# DENAS_Scheme.net
KiCad netlist of a schematic drawn in Altium Designer
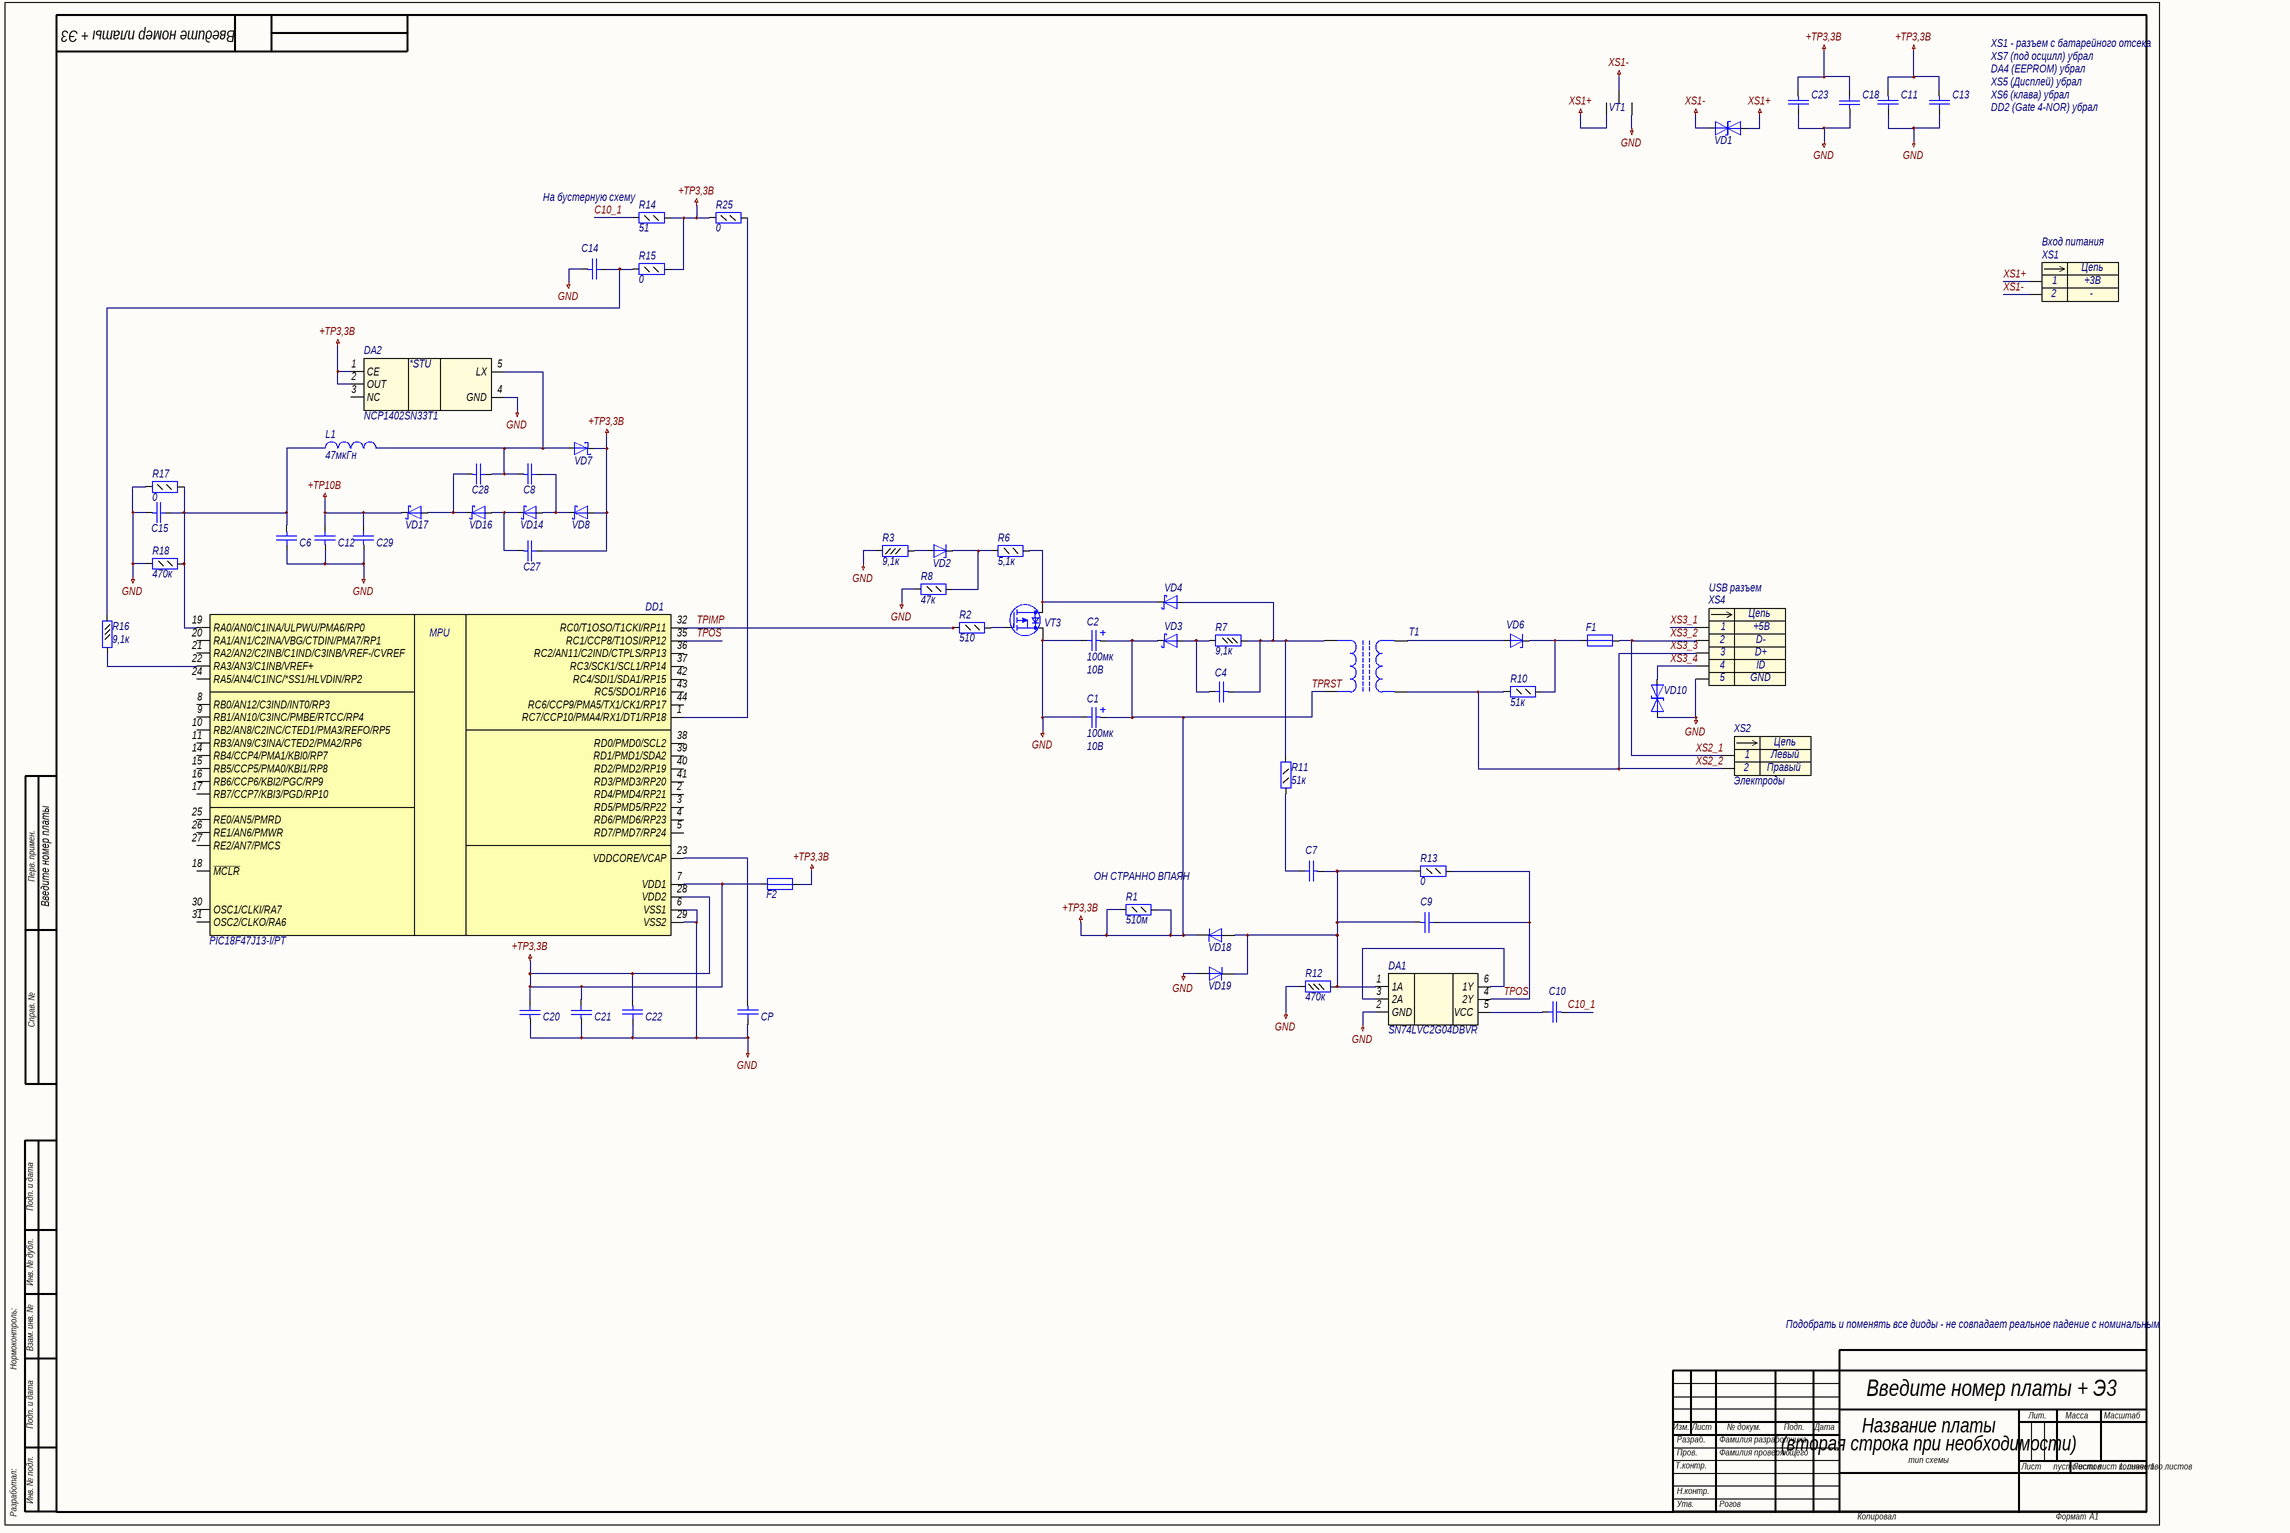
[diagram p0: DENAS_Scheme.SchDoc]

(export (version "E")
  (design (tool "Eeschema 10.0.6"))
  (components
    (comp (ref "C1")
      (value "100мк")
      (footprint "TANTAL CASE D")
      (description "Конденсатор полярный")
      (fields
        (field (name "VOLTAGE") "10В")
        (field (name "PART NUMBER") "T495D107K010ATA080")
        (field (name "Comment") "Capacitor_pol")
      )
      (libsource (lib "MOP44") (part "Capacitor_pol"))
    )
    (comp (ref "C2")
      (value "100мк")
      (footprint "TANTAL CASE D")
      (description "Конденсатор полярный")
      (fields
        (field (name "VOLTAGE") "10В")
        (field (name "PART NUMBER") "T495D107K010ATA080")
        (field (name "Comment") "Capacitor_pol")
      )
      (libsource (lib "MOP44") (part "Capacitor_pol"))
    )
    (comp (ref "C4")
      (value "Capacitor")
      (footprint "C0402")
      (description "Конденсатор")
      (fields (field (name "VOLTAGE") "50B") (field (name "PART NUMBER") "GRP1555C1HR47CZ01E"))
      (libsource (lib "MOP44") (part "Capacitor"))
    )
    (comp (ref "C6")
      (value "Capacitor")
      (footprint "C0402")
      (description "Конденсатор")
      (fields (field (name "VOLTAGE") "50B") (field (name "PART NUMBER") "GRP1555C1HR47CZ01E"))
      (libsource (lib "MOP44") (part "Capacitor"))
    )
    (comp (ref "C7")
      (value "Capacitor")
      (footprint "C0402")
      (description "Конденсатор")
      (fields (field (name "VOLTAGE") "50B") (field (name "PART NUMBER") "GRP1555C1HR47CZ01E"))
      (libsource (lib "MOP44") (part "Capacitor"))
    )
    (comp (ref "C8")
      (value "Capacitor")
      (footprint "C0402")
      (description "Конденсатор")
      (fields (field (name "VOLTAGE") "50B") (field (name "PART NUMBER") "GRP1555C1HR47CZ01E"))
      (libsource (lib "MOP44") (part "Capacitor"))
    )
    (comp (ref "C9")
      (value "Capacitor")
      (footprint "C0402")
      (description "Конденсатор")
      (fields (field (name "VOLTAGE") "50B") (field (name "PART NUMBER") "GRP1555C1HR47CZ01E"))
      (libsource (lib "MOP44") (part "Capacitor"))
    )
    (comp (ref "C10")
      (value "Capacitor")
      (footprint "C0402")
      (description "Конденсатор")
      (fields (field (name "VOLTAGE") "50B") (field (name "PART NUMBER") "GRP1555C1HR47CZ01E"))
      (libsource (lib "MOP44") (part "Capacitor"))
    )
    (comp (ref "C11")
      (value "Capacitor")
      (footprint "C0402")
      (description "Конденсатор")
      (fields (field (name "VOLTAGE") "50B") (field (name "PART NUMBER") "GRP1555C1HR47CZ01E"))
      (libsource (lib "MOP44") (part "Capacitor"))
    )
    (comp (ref "C12")
      (value "Capacitor")
      (footprint "C0402")
      (description "Конденсатор")
      (fields (field (name "VOLTAGE") "50B") (field (name "PART NUMBER") "GRP1555C1HR47CZ01E"))
      (libsource (lib "MOP44") (part "Capacitor"))
    )
    (comp (ref "C13")
      (value "Capacitor")
      (footprint "C0402")
      (description "Конденсатор")
      (fields (field (name "VOLTAGE") "50B") (field (name "PART NUMBER") "GRP1555C1HR47CZ01E"))
      (libsource (lib "MOP44") (part "Capacitor"))
    )
    (comp (ref "C14")
      (value "Capacitor")
      (footprint "C0402")
      (description "Конденсатор")
      (fields (field (name "VOLTAGE") "50B") (field (name "PART NUMBER") "GRP1555C1HR47CZ01E"))
      (libsource (lib "MOP44") (part "Capacitor"))
    )
    (comp (ref "C15")
      (value "Capacitor")
      (footprint "C0402")
      (description "Конденсатор")
      (fields (field (name "VOLTAGE") "50B") (field (name "PART NUMBER") "GRP1555C1HR47CZ01E"))
      (libsource (lib "MOP44") (part "Capacitor"))
    )
    (comp (ref "C18")
      (value "Capacitor")
      (footprint "C0402")
      (description "Конденсатор")
      (fields (field (name "VOLTAGE") "50B") (field (name "PART NUMBER") "GRP1555C1HR47CZ01E"))
      (libsource (lib "MOP44") (part "Capacitor"))
    )
    (comp (ref "C20")
      (value "Capacitor")
      (footprint "C0402")
      (description "Конденсатор")
      (fields (field (name "VOLTAGE") "50B") (field (name "PART NUMBER") "GRP1555C1HR47CZ01E"))
      (libsource (lib "MOP44") (part "Capacitor"))
    )
    (comp (ref "C21")
      (value "Capacitor")
      (footprint "C0402")
      (description "Конденсатор")
      (fields (field (name "VOLTAGE") "50B") (field (name "PART NUMBER") "GRP1555C1HR47CZ01E"))
      (libsource (lib "MOP44") (part "Capacitor"))
    )
    (comp (ref "C22")
      (value "Capacitor")
      (footprint "C0402")
      (description "Конденсатор")
      (fields (field (name "VOLTAGE") "50B") (field (name "PART NUMBER") "GRP1555C1HR47CZ01E"))
      (libsource (lib "MOP44") (part "Capacitor"))
    )
    (comp (ref "C23")
      (value "Capacitor")
      (footprint "C0402")
      (description "Конденсатор")
      (fields (field (name "VOLTAGE") "50B") (field (name "PART NUMBER") "GRP1555C1HR47CZ01E"))
      (libsource (lib "MOP44") (part "Capacitor"))
    )
    (comp (ref "C27")
      (value "Capacitor")
      (footprint "C0402")
      (description "Конденсатор")
      (fields (field (name "VOLTAGE") "50B") (field (name "PART NUMBER") "GRP1555C1HR47CZ01E"))
      (libsource (lib "MOP44") (part "Capacitor"))
    )
    (comp (ref "C28")
      (value "Capacitor")
      (footprint "C0402")
      (description "Конденсатор")
      (fields (field (name "VOLTAGE") "50B") (field (name "PART NUMBER") "GRP1555C1HR47CZ01E"))
      (libsource (lib "MOP44") (part "Capacitor"))
    )
    (comp (ref "C29")
      (value "Capacitor")
      (footprint "C0402")
      (description "Конденсатор")
      (fields (field (name "VOLTAGE") "50B") (field (name "PART NUMBER") "GRP1555C1HR47CZ01E"))
      (libsource (lib "MOP44") (part "Capacitor"))
    )
    (comp (ref "CP")
      (value "Capacitor")
      (footprint "C0402")
      (description "Конденсатор")
      (fields (field (name "VOLTAGE") "50B") (field (name "PART NUMBER") "GRP1555C1HR47CZ01E"))
      (libsource (lib "MOP44") (part "Capacitor"))
    )
    (comp (ref "DA1")
      (value "SN74LVC2G04DBVR")
      (footprint "SOT23-6")
      (description "Инвертирующий Триггер Шмитта")
      (fields (field (name "PART NUMBER") "SN74LVC2G04DBVR"))
      (libsource (lib "MOP44") (part "SN74LVC2G04DBVR"))
    )
    (comp (ref "DA2")
      (value "NCP1402")
      (footprint "SOT23-5")
      (description "Step-up DC-DC Converter for 2-V to 3.3-V")
      (fields (field (name "PART NUMBER") "NCP1402SN33T1") (field (name "MANUFACTURER") "ON Semiconductor"))
      (libsource (lib "MOP44") (part "NCP1402"))
    )
    (comp (ref "DD1")
      (value "PIC18F47J13-I/PT")
      (footprint "TQFP-44")
      (description "Микроконтроллер 8-Бит, 44-pin")
      (libsource (lib "MOP44") (part "PIC18F47J13-I/PT"))
    )
    (comp (ref "F1")
      (value "Fuse")
      (footprint "FUSE812")
      (description "Предохранитель")
      (fields (field (name "PART NUMBER") "MF-MSMF050"))
      (libsource (lib "") (part "Fuse_1"))
    )
    (comp (ref "F2")
      (value "Fuse")
      (footprint "FUSE812")
      (description "Предохранитель")
      (fields (field (name "PART NUMBER") "MF-MSMF075"))
      (libsource (lib "MOP44") (part "Fuse"))
    )
    (comp (ref "L1")
      (value "47мкГн")
      (footprint "SDR0604")
      (description "EMI Suppression Filter")
      (fields (field (name "PART NUMBER") "SDR0604- 470KL") (field (name "Comment") "Inductor"))
      (libsource (lib "MOP44") (part "Inductor"))
    )
    (comp (ref "R1")
      (value "510м")
      (footprint "R0805")
      (description "Резистор")
      (fields (field (name "PART NUMBER") "RC0805FR-07510RL") (field (name "POWER") "0,125Вт"))
      (libsource (lib "MOP44") (part "Resistor_0,125Вт"))
    )
    (comp (ref "R2")
      (value "510")
      (footprint "R0805")
      (description "Резистор")
      (fields (field (name "PART NUMBER") "RC0805FR-07510RL") (field (name "POWER") "0,125Вт"))
      (libsource (lib "MOP44") (part "Resistor_0,125Вт"))
    )
    (comp (ref "R3")
      (value "9,1к")
      (footprint "R0603")
      (description "Резистор")
      (fields (field (name "PART NUMBER") "RC0603FR-079K1") (field (name "POWER") "0,062Вт"))
      (libsource (lib "") (part "Resistor_0,062Вт_3"))
    )
    (comp (ref "R6")
      (value "5,1к")
      (footprint "R0805")
      (description "Резистор")
      (fields (field (name "PART NUMBER") "RC0805FR-075K1") (field (name "POWER") "0,125Вт"))
      (libsource (lib "MOP44") (part "Resistor_0,125Вт"))
    )
    (comp (ref "R7")
      (value "9,1к")
      (footprint "R0603")
      (description "Резистор")
      (fields (field (name "PART NUMBER") "RC0603FR-079K1") (field (name "POWER") "0,062Вт"))
      (libsource (lib "MOP44") (part "Resistor_0,062Вт"))
    )
    (comp (ref "R8")
      (value "47к")
      (footprint "R0805")
      (description "Резистор")
      (fields (field (name "PART NUMBER") "RC0805FR-0747KL") (field (name "POWER") "0,125Вт"))
      (libsource (lib "MOP44") (part "Resistor_0,125Вт"))
    )
    (comp (ref "R10")
      (value "51к")
      (footprint "R0805")
      (description "Резистор")
      (fields (field (name "PART NUMBER") "RC0805FR-0751KL") (field (name "POWER") "0,125Вт"))
      (libsource (lib "MOP44") (part "Resistor_0,125Вт"))
    )
    (comp (ref "R11")
      (value "51к")
      (footprint "R0805")
      (description "Резистор")
      (fields (field (name "PART NUMBER") "RC0805FR-0751KL") (field (name "POWER") "0,125Вт"))
      (libsource (lib "") (part "Resistor_0,125Вт_2"))
    )
    (comp (ref "R12")
      (value "470к")
      (footprint "R0603")
      (description "Резистор")
      (fields (field (name "PART NUMBER") "RC0603FR-07470KL") (field (name "POWER") "0,062Вт"))
      (libsource (lib "") (part "Resistor_0,062Вт_2"))
    )
    (comp (ref "R13")
      (value "0")
      (footprint "R0805")
      (description "Резистор")
      (fields (field (name "PART NUMBER") "RC0805FR-070RL") (field (name "POWER") "0,125Вт"))
      (libsource (lib "MOP44") (part "Resistor_0,125Вт"))
    )
    (comp (ref "R14")
      (value "51")
      (footprint "R0805")
      (description "Резистор")
      (fields (field (name "PART NUMBER") "RC0805FR-0751RL") (field (name "POWER") "0,125Вт"))
      (libsource (lib "") (part "Resistor_0,125Вт_1"))
    )
    (comp (ref "R15")
      (value "0")
      (footprint "R0805")
      (description "Резистор")
      (fields (field (name "PART NUMBER") "RC0805FR-070RL") (field (name "POWER") "0,125Вт"))
      (libsource (lib "") (part "Resistor_0,125Вт_1"))
    )
    (comp (ref "R16")
      (value "9,1к")
      (footprint "R0603")
      (description "Резистор")
      (fields (field (name "PART NUMBER") "RC0603FR-079K1") (field (name "POWER") "0,062Вт"))
      (libsource (lib "") (part "Resistor_0,062Вт_1"))
    )
    (comp (ref "R17")
      (value "0")
      (footprint "R0805")
      (description "Резистор")
      (fields (field (name "PART NUMBER") "RC0805FR-070RL") (field (name "POWER") "0,125Вт"))
      (libsource (lib "") (part "Resistor_0,125Вт_1"))
    )
    (comp (ref "R18")
      (value "470к")
      (footprint "R0805")
      (description "Резистор")
      (fields (field (name "PART NUMBER") "RC0805FR-07470KL") (field (name "POWER") "0,125Вт"))
      (libsource (lib "MOP44") (part "Resistor_0,125Вт"))
    )
    (comp (ref "R25")
      (value "0")
      (footprint "R0805")
      (description "Резистор")
      (fields (field (name "PART NUMBER") "RC0805FR-070RL") (field (name "POWER") "0,125Вт"))
      (libsource (lib "") (part "Resistor_0,125Вт_1"))
    )
    (comp (ref "T1")
      (value "Transformer")
      (footprint "Transformer36mm")
      (description "EMI Suppression Filter")
      (libsource (lib "MOP44") (part "Transformer"))
    )
    (comp (ref "VD1")
      (value "DiodeZenerDual")
      (footprint "SMB")
      (description "Cтабилитрон (диод выпрямительный лавинный) двусторонний")
      (fields (field (name "PART NUMBER") "SMBJ8.5CA"))
      (libsource (lib "MOP44") (part "DiodeZenerDual"))
    )
    (comp (ref "VD2")
      (value "DiodeZener")
      (footprint "SOT23-3")
      (description "Cтабилитрон (лавинный выпрямительный диод) односторонний")
      (fields (field (name "PART NUMBER") "BZX84-C30"))
      (libsource (lib "MOP44") (part "DiodeZener"))
    )
    (comp (ref "VD3")
      (value "DiodeSchottky")
      (footprint "SOD-123")
      (description "Диод Шоттки")
      (fields (field (name "PART NUMBER") "MBR0540"))
      (libsource (lib "MOP44") (part "DiodeSchottky"))
    )
    (comp (ref "VD4")
      (value "DiodeSchottky")
      (footprint "SOD-123")
      (description "Диод Шоттки")
      (fields (field (name "PART NUMBER") "MBR0540"))
      (libsource (lib "MOP44") (part "DiodeSchottky"))
    )
    (comp (ref "VD6")
      (value "DiodeZener")
      (footprint "SOT23-3")
      (description "Cтабилитрон (лавинный выпрямительный диод) односторонний")
      (fields (field (name "PART NUMBER") "BZX84-C5V1"))
      (libsource (lib "MOP44") (part "DiodeZener"))
    )
    (comp (ref "VD7")
      (value "DiodeSchottky")
      (footprint "SOD-123")
      (description "Диод Шоттки")
      (fields (field (name "PART NUMBER") "MBR0520LT1"))
      (libsource (lib "MOP44") (part "DiodeSchottky"))
    )
    (comp (ref "VD8")
      (value "DiodeSchottky")
      (footprint "SOD-123")
      (description "Диод Шоттки")
      (fields (field (name "PART NUMBER") "MBR0520LT1"))
      (libsource (lib "MOP44") (part "DiodeSchottky"))
    )
    (comp (ref "VD10")
      (value "DiodeZenerDual")
      (footprint "SMB")
      (description "Cтабилитрон (диод выпрямительный лавинный) двусторонний")
      (fields (field (name "PART NUMBER") "SMBJ8.5CA"))
      (libsource (lib "MOP44") (part "DiodeZenerDual"))
    )
    (comp (ref "VD14")
      (value "DiodeSchottky")
      (footprint "SOD-123")
      (description "Диод Шоттки")
      (fields (field (name "PART NUMBER") "MBR0520LT1"))
      (libsource (lib "MOP44") (part "DiodeSchottky"))
    )
    (comp (ref "VD16")
      (value "DiodeSchottky")
      (footprint "SOD-123")
      (description "Диод Шоттки")
      (fields (field (name "PART NUMBER") "MBR0520LT1"))
      (libsource (lib "MOP44") (part "DiodeSchottky"))
    )
    (comp (ref "VD17")
      (value "DiodeSchottky")
      (footprint "SOD-123")
      (description "Диод Шоттки")
      (fields (field (name "PART NUMBER") "MBR0520LT1"))
      (libsource (lib "MOP44") (part "DiodeSchottky"))
    )
    (comp (ref "VD18")
      (value "Diode")
      (footprint "SOD-123")
      (description "Диод")
      (fields (field (name "PART NUMBER") "MMSD4148"))
      (libsource (lib "MOP44") (part "Diode"))
    )
    (comp (ref "VD19")
      (value "Diode")
      (footprint "SOD-123")
      (description "Диод")
      (fields (field (name "PART NUMBER") "MMSD4148"))
      (libsource (lib "MOP44") (part "Diode"))
    )
    (comp (ref "VT3")
      (value "P-MOSFET")
      (footprint "SOT23-3")
      (description "N-MOSFET")
      (fields
        (field (name "PART NUMBER") "IRLML2244TRPbF")
        (field (name "MANUFACTURER") "International Rectifier")
      )
      (libsource (lib "MOP44") (part "P-MOSFET"))
    )
    (comp (ref "XS1")
      (value "Вход питания")
      (footprint "CWF-2")
      (description "Разъем - 2 конт. вилка")
      (fields (field (name "PART NUMBER") "DS1069-2MVW6X"))
      (libsource (lib "MOP44") (part "Header_2_plg"))
    )
    (comp (ref "XS2")
      (value "Электроды")
      (footprint "CWF-2")
      (description "Разъем - 2 конт. вилка")
      (fields (field (name "PART NUMBER") "DS1069-2MVW6X"))
      (libsource (lib "MOP44") (part "Header_2_plg"))
    )
    (comp (ref "XS4")
      (value "USB разъем")
      (footprint "USB MINI AB RECEPTACLE")
      (description "USB Mini Type AB Receptacle")
      (fields (field (name "PART NUMBER") "UJ2-MABH-1-SMT-TR"))
      (libsource (lib "MOP44") (part "USB MINI RECEPTACLE"))
    )
  )
  (nets
    (net (code "1") (name "+TP3,3В") (class "Default")
      (node (ref "C1") (pin "1") (pinfunction "1_1") (pintype "passive"))
      (node (ref "C11") (pin "1") (pinfunction "1_1") (pintype "passive"))
      (node (ref "C13") (pin "1") (pinfunction "1_1") (pintype "passive"))
      (node (ref "C18") (pin "2") (pinfunction "2_2") (pintype "passive"))
      (node (ref "C2") (pin "1") (pinfunction "1_1") (pintype "passive"))
      (node (ref "C20") (pin "2") (pinfunction "2_2") (pintype "passive"))
      (node (ref "C21") (pin "2") (pinfunction "2_2") (pintype "passive"))
      (node (ref "C22") (pin "1") (pinfunction "1_1") (pintype "passive"))
      (node (ref "C23") (pin "1") (pinfunction "1_1") (pintype "passive"))
      (node (ref "C27") (pin "2") (pinfunction "2_2") (pintype "passive"))
      (node (ref "DA2") (pin "1") (pinfunction "CE_1") (pintype "power_in"))
      (node (ref "DA2") (pin "2") (pinfunction "OUT_2") (pintype "power_in"))
      (node (ref "DD1") (pin "28") (pinfunction "VDD2_28") (pintype "passive"))
      (node (ref "DD1") (pin "7") (pinfunction "VDD1_7") (pintype "passive"))
      (node (ref "F2") (pin "1") (pinfunction "1_1") (pintype "passive"))
      (node (ref "F2") (pin "2") (pinfunction "2_2") (pintype "passive"))
      (node (ref "R1") (pin "1") (pinfunction "1_1") (pintype "passive"))
      (node (ref "R1") (pin "2") (pinfunction "2_2") (pintype "passive"))
      (node (ref "R14") (pin "2") (pinfunction "2_2") (pintype "passive"))
      (node (ref "R15") (pin "2") (pinfunction "2_2") (pintype "passive"))
      (node (ref "R25") (pin "1") (pinfunction "1_1") (pintype "passive"))
      (node (ref "T1") (pin "2") (pinfunction "2_2") (pintype "passive"))
      (node (ref "VD18") (pin "1") (pinfunction "K_1") (pintype "passive"))
      (node (ref "VD3") (pin "1") (pinfunction "K_1") (pintype "passive"))
      (node (ref "VD7") (pin "1") (pinfunction "K_1") (pintype "passive"))
      (node (ref "VD8") (pin "2") (pinfunction "A_2") (pintype "passive"))
    )
    (net (code "2") (name "+TP10В") (class "Default")
      (node (ref "C12") (pin "2") (pinfunction "2_2") (pintype "passive"))
      (node (ref "C29") (pin "2") (pinfunction "2_2") (pintype "passive"))
      (node (ref "VD17") (pin "1") (pinfunction "K_1") (pintype "passive"))
    )
    (net (code "3") (name "/C10_1") (class "Default")
      (node (ref "C10") (pin "1") (pinfunction "1_1") (pintype "passive"))
      (node (ref "R14") (pin "1") (pinfunction "1_1") (pintype "passive"))
    )
    (net (code "4") (name "/TPIMP") (class "Default")
      (node (ref "DD1") (pin "32") (pinfunction "RC0/T1OSO/T1CKI/RP11_32") (pintype "passive"))
      (node (ref "R2") (pin "2") (pinfunction "2_2") (pintype "passive"))
    )
    (net (code "5") (name "/TPOS") (class "Default")
      (node (ref "C9") (pin "2") (pinfunction "2_2") (pintype "passive"))
      (node (ref "DA1") (pin "4") (pinfunction "2Y_4") (pintype "power_in"))
      (node (ref "DD1") (pin "35") (pinfunction "RC1/CCP8/T1OSI/RP12_35") (pintype "passive"))
      (node (ref "R13") (pin "1") (pinfunction "1_1") (pintype "passive"))
    )
    (net (code "6") (name "/XS2_1") (class "Default")
      (node (ref "F1") (pin "1") (pinfunction "1_1") (pintype "passive"))
      (node (ref "XS2") (pin "1") (pinfunction "1_1") (pintype "passive"))
      (node (ref "XS4") (pin "2") (pinfunction "2_2") (pintype "passive"))
    )
    (net (code "7") (name "/XS2_2") (class "Default")
      (node (ref "R10") (pin "2") (pinfunction "2_2") (pintype "passive"))
      (node (ref "T1") (pin "4") (pinfunction "4_4") (pintype "passive"))
      (node (ref "XS2") (pin "2") (pinfunction "2_2") (pintype "passive"))
      (node (ref "XS4") (pin "3") (pinfunction "3_3") (pintype "passive"))
    )
    (net (code "8") (name "/XS3_1") (class "Default")
      (node (ref "XS4") (pin "1") (pinfunction "1_1") (pintype "passive"))
    )
    (net (code "9") (name "/XS3_4") (class "Default")
      (node (ref "VD10") (pin "2") (pinfunction "A_2") (pintype "passive"))
      (node (ref "XS4") (pin "4") (pinfunction "4_4") (pintype "passive"))
    )
    (net (code "10") (name "GND") (class "Default")
      (node (ref "C1") (pin "2") (pinfunction "2_2") (pintype "passive"))
      (node (ref "C11") (pin "2") (pinfunction "2_2") (pintype "passive"))
      (node (ref "C12") (pin "1") (pinfunction "1_1") (pintype "passive"))
      (node (ref "C13") (pin "2") (pinfunction "2_2") (pintype "passive"))
      (node (ref "C14") (pin "1") (pinfunction "1_1") (pintype "passive"))
      (node (ref "C15") (pin "1") (pinfunction "1_1") (pintype "passive"))
      (node (ref "C18") (pin "1") (pinfunction "1_1") (pintype "passive"))
      (node (ref "C2") (pin "2") (pinfunction "2_2") (pintype "passive"))
      (node (ref "C20") (pin "1") (pinfunction "1_1") (pintype "passive"))
      (node (ref "C21") (pin "1") (pinfunction "1_1") (pintype "passive"))
      (node (ref "C22") (pin "2") (pinfunction "2_2") (pintype "passive"))
      (node (ref "C23") (pin "2") (pinfunction "2_2") (pintype "passive"))
      (node (ref "C29") (pin "1") (pinfunction "1_1") (pintype "passive"))
      (node (ref "C6") (pin "2") (pinfunction "2_2") (pintype "passive"))
      (node (ref "CP") (pin "2") (pinfunction "2_2") (pintype "passive"))
      (node (ref "DA1") (pin "2") (pinfunction "GND_2") (pintype "power_in"))
      (node (ref "DA2") (pin "4") (pinfunction "GND_4") (pintype "power_in"))
      (node (ref "DD1") (pin "29") (pinfunction "VSS2_29") (pintype "passive"))
      (node (ref "DD1") (pin "6") (pinfunction "VSS1_6") (pintype "passive"))
      (node (ref "R12") (pin "1") (pinfunction "1_1") (pintype "passive"))
      (node (ref "R17") (pin "1") (pinfunction "1_1") (pintype "passive"))
      (node (ref "R18") (pin "2") (pinfunction "2_2") (pintype "passive"))
      (node (ref "R3") (pin "1") (pinfunction "1_1") (pintype "passive"))
      (node (ref "R8") (pin "2") (pinfunction "2_2") (pintype "passive"))
      (node (ref "VD10") (pin "1") (pinfunction "K_1") (pintype "passive"))
      (node (ref "VD19") (pin "2") (pinfunction "A_2") (pintype "passive"))
      (node (ref "VT3") (pin "3") (pinfunction "S_3") (pintype "passive"))
      (node (ref "XS4") (pin "5") (pinfunction "5_5") (pintype "passive"))
    )
    (net (code "11") (name "Net-(C7-Pad2)") (class "Default")
      (node (ref "C7") (pin "2") (pinfunction "2_2") (pintype "passive"))
      (node (ref "R11") (pin "1") (pinfunction "1_1") (pintype "passive"))
    )
    (net (code "12") (name "Net-(C14-Pad2)") (class "Default")
      (node (ref "C14") (pin "2") (pinfunction "2_2") (pintype "passive"))
      (node (ref "R15") (pin "1") (pinfunction "1_1") (pintype "passive"))
      (node (ref "R16") (pin "1") (pinfunction "1_1") (pintype "passive"))
    )
    (net (code "13") (name "Net-(DA1-1A)") (class "Default")
      (node (ref "C7") (pin "1") (pinfunction "1_1") (pintype "passive"))
      (node (ref "C9") (pin "1") (pinfunction "1_1") (pintype "passive"))
      (node (ref "DA1") (pin "1") (pinfunction "1A_1") (pintype "power_in"))
      (node (ref "R12") (pin "2") (pinfunction "2_2") (pintype "passive"))
      (node (ref "R13") (pin "2") (pinfunction "2_2") (pintype "passive"))
      (node (ref "VD18") (pin "2") (pinfunction "A_2") (pintype "passive"))
      (node (ref "VD19") (pin "1") (pinfunction "K_1") (pintype "passive"))
    )
    (net (code "14") (name "Net-(DA1-1Y)") (class "Default")
      (node (ref "DA1") (pin "3") (pinfunction "2A_3") (pintype "power_in"))
      (node (ref "DA1") (pin "6") (pinfunction "1Y_6") (pintype "power_in"))
    )
    (net (code "15") (name "Net-(DA1-VCC)") (class "Default")
      (node (ref "C10") (pin "2") (pinfunction "2_2") (pintype "passive"))
      (node (ref "DA1") (pin "5") (pinfunction "VCC_5") (pintype "power_in"))
    )
    (net (code "16") (name "Net-(DA2-LX)") (class "Default")
      (node (ref "C28") (pin "2") (pinfunction "2_2") (pintype "passive"))
      (node (ref "C8") (pin "1") (pinfunction "1_1") (pintype "passive"))
      (node (ref "DA2") (pin "5") (pinfunction "LX_5") (pintype "power_in"))
      (node (ref "L1") (pin "1") (pinfunction "1_1") (pintype "passive"))
      (node (ref "VD7") (pin "2") (pinfunction "A_2") (pintype "passive"))
    )
    (net (code "17") (name "Net-(DD1-RA0{slash}AN0{slash}C1INA{slash}ULPWU{slash}PMA6{slash}RP0)") (class "Default")
      (node (ref "C15") (pin "2") (pinfunction "2_2") (pintype "passive"))
      (node (ref "C6") (pin "1") (pinfunction "1_1") (pintype "passive"))
      (node (ref "DD1") (pin "19") (pinfunction "RA0/AN0/C1INA/ULPWU/PMA6/RP0_19") (pintype "passive"))
      (node (ref "L1") (pin "2") (pinfunction "2_2") (pintype "passive"))
      (node (ref "R17") (pin "2") (pinfunction "2_2") (pintype "passive"))
      (node (ref "R18") (pin "1") (pinfunction "1_1") (pintype "passive"))
    )
    (net (code "18") (name "Net-(DD1-RA3{slash}AN3{slash}C1INB{slash}VREF+)") (class "Default")
      (node (ref "DD1") (pin "22") (pinfunction "RA3/AN3/C1INB/VREF+_22") (pintype "passive"))
      (node (ref "R16") (pin "2") (pinfunction "2_2") (pintype "passive"))
    )
    (net (code "19") (name "Net-(DD1-RC7{slash}CCP10{slash}PMA4{slash}RX1{slash}DT1{slash}RP18)") (class "Default")
      (node (ref "DD1") (pin "1") (pinfunction "RC7/CCP10/PMA4/RX1/DT1/RP18_1") (pintype "passive"))
      (node (ref "R25") (pin "2") (pinfunction "2_2") (pintype "passive"))
    )
    (net (code "20") (name "Net-(DD1-VDDCORE{slash}VCAP)") (class "Default")
      (node (ref "CP") (pin "1") (pinfunction "1_1") (pintype "passive"))
      (node (ref "DD1") (pin "23") (pinfunction "VDDCORE/VCAP_23") (pintype "passive"))
    )
    (net (code "21") (name "Net-(VD2-A)") (class "Default")
      (node (ref "R3") (pin "2") (pinfunction "2_2") (pintype "passive"))
      (node (ref "VD2") (pin "2") (pinfunction "A_2") (pintype "passive"))
    )
    (net (code "22") (name "Net-(VD2-K)") (class "Default")
      (node (ref "R6") (pin "2") (pinfunction "2_2") (pintype "passive"))
      (node (ref "R8") (pin "1") (pinfunction "1_1") (pintype "passive"))
      (node (ref "VD2") (pin "1") (pinfunction "K_1") (pintype "passive"))
    )
    (net (code "23") (name "Net-(VD3-A)") (class "Default")
      (node (ref "C4") (pin "2") (pinfunction "2_2") (pintype "passive"))
      (node (ref "R7") (pin "2") (pinfunction "2_2") (pintype "passive"))
      (node (ref "VD3") (pin "2") (pinfunction "A_2") (pintype "passive"))
    )
    (net (code "24") (name "Net-(VD4-A)") (class "Default")
      (node (ref "C4") (pin "1") (pinfunction "1_1") (pintype "passive"))
      (node (ref "R11") (pin "2") (pinfunction "2_2") (pintype "passive"))
      (node (ref "R7") (pin "1") (pinfunction "1_1") (pintype "passive"))
      (node (ref "T1") (pin "1") (pinfunction "1_1") (pintype "passive"))
      (node (ref "VD4") (pin "2") (pinfunction "A_2") (pintype "passive"))
    )
    (net (code "25") (name "Net-(VD4-K)") (class "Default")
      (node (ref "R6") (pin "1") (pinfunction "1_1") (pintype "passive"))
      (node (ref "VD4") (pin "1") (pinfunction "K_1") (pintype "passive"))
      (node (ref "VT3") (pin "2") (pinfunction "D_2") (pintype "passive"))
    )
    (net (code "26") (name "Net-(VD6-A)") (class "Default")
      (node (ref "T1") (pin "3") (pinfunction "3_3") (pintype "passive"))
      (node (ref "VD6") (pin "2") (pinfunction "A_2") (pintype "passive"))
    )
    (net (code "27") (name "Net-(VD6-K)") (class "Default")
      (node (ref "F1") (pin "2") (pinfunction "2_2") (pintype "passive"))
      (node (ref "R10") (pin "1") (pinfunction "1_1") (pintype "passive"))
      (node (ref "VD6") (pin "1") (pinfunction "K_1") (pintype "passive"))
    )
    (net (code "28") (name "Net-(VD14-A)") (class "Default")
      (node (ref "C8") (pin "2") (pinfunction "2_2") (pintype "passive"))
      (node (ref "VD14") (pin "2") (pinfunction "A_2") (pintype "passive"))
      (node (ref "VD8") (pin "1") (pinfunction "K_1") (pintype "passive"))
    )
    (net (code "29") (name "Net-(VD14-K)") (class "Default")
      (node (ref "C27") (pin "1") (pinfunction "1_1") (pintype "passive"))
      (node (ref "VD14") (pin "1") (pinfunction "K_1") (pintype "passive"))
      (node (ref "VD16") (pin "2") (pinfunction "A_2") (pintype "passive"))
    )
    (net (code "30") (name "Net-(VD16-K)") (class "Default")
      (node (ref "C28") (pin "1") (pinfunction "1_1") (pintype "passive"))
      (node (ref "VD16") (pin "1") (pinfunction "K_1") (pintype "passive"))
      (node (ref "VD17") (pin "2") (pinfunction "A_2") (pintype "passive"))
    )
    (net (code "31") (name "Net-(VT3-G)") (class "Default")
      (node (ref "R2") (pin "1") (pinfunction "1_1") (pintype "passive"))
      (node (ref "VT3") (pin "1") (pinfunction "G_1") (pintype "passive"))
    )
    (net (code "32") (name "XS1+") (class "Default")
      (node (ref "VD1") (pin "1") (pinfunction "K_1") (pintype "passive"))
      (node (ref "XS1") (pin "1") (pinfunction "1_1") (pintype "passive"))
    )
    (net (code "33") (name "XS1-") (class "Default")
      (node (ref "VD1") (pin "2") (pinfunction "A_2") (pintype "passive"))
      (node (ref "XS1") (pin "2") (pinfunction "2_2") (pintype "passive"))
    )
    (net (code "34") (name "unconnected-(DA2-NC-Pad3)") (class "Default")
      (node (ref "DA2") (pin "3") (pinfunction "NC_3") (pintype "power_in"))
    )
    (net (code "35") (name "unconnected-(DD1-OSC1{slash}CLKI{slash}RA7-Pad30)") (class "Default")
      (node (ref "DD1") (pin "30") (pinfunction "OSC1/CLKI/RA7_30") (pintype "passive"))
    )
    (net (code "36") (name "unconnected-(DD1-OSC2{slash}CLKO{slash}RA6-Pad31)") (class "Default")
      (node (ref "DD1") (pin "31") (pinfunction "OSC2/CLKO/RA6_31") (pintype "passive"))
    )
    (net (code "37") (name "unconnected-(DD1-RA1{slash}AN1{slash}C2INA{slash}VBG{slash}CTDIN{slash}PMA7{slash}RP1-Pad20)") (class "Default")
      (node (ref "DD1") (pin "20") (pinfunction "RA1/AN1/C2INA/VBG/CTDIN/PMA7/RP1_20") (pintype "passive"))
    )
    (net (code "38") (name "unconnected-(DD1-RA2{slash}AN2{slash}C2INB{slash}C1IND{slash}C3INB{slash}VREF-{slash}CVREF-Pad21)") (class "Default")
      (node (ref "DD1") (pin "21") (pinfunction "RA2/AN2/C2INB/C1IND/C3INB/VREF-/CVREF_21") (pintype "passive"))
    )
    (net (code "39") (name "unconnected-(DD1-RA5{slash}AN4{slash}C1INC{slash}*SS1{slash}HLVDIN{slash}RP2-Pad24)") (class "Default")
      (node (ref "DD1") (pin "24") (pinfunction "RA5/AN4/C1INC/*SS1/HLVDIN/RP2_24") (pintype "passive"))
    )
    (net (code "40") (name "unconnected-(DD1-RB0{slash}AN12{slash}C3IND{slash}INT0{slash}RP3-Pad8)") (class "Default")
      (node (ref "DD1") (pin "8") (pinfunction "RB0/AN12/C3IND/INT0/RP3_8") (pintype "passive"))
    )
    (net (code "41") (name "unconnected-(DD1-RB1{slash}AN10{slash}C3INC{slash}PMBE{slash}RTCC{slash}RP4-Pad9)") (class "Default")
      (node (ref "DD1") (pin "9") (pinfunction "RB1/AN10/C3INC/PMBE/RTCC/RP4_9") (pintype "passive"))
    )
    (net (code "42") (name "unconnected-(DD1-RB2{slash}AN8{slash}C2INC{slash}CTED1{slash}PMA3{slash}REFO{slash}RP5-Pad10)") (class "Default")
      (node (ref "DD1") (pin "10") (pinfunction "RB2/AN8/C2INC/CTED1/PMA3/REFO/RP5_10") (pintype "passive"))
    )
    (net (code "43") (name "unconnected-(DD1-RB3{slash}AN9{slash}C3INA{slash}CTED2{slash}PMA2{slash}RP6-Pad11)") (class "Default")
      (node (ref "DD1") (pin "11") (pinfunction "RB3/AN9/C3INA/CTED2/PMA2/RP6_11") (pintype "passive"))
    )
    (net (code "44") (name "unconnected-(DD1-RB4{slash}CCP4{slash}PMA1{slash}KBI0{slash}RP7-Pad14)") (class "Default")
      (node (ref "DD1") (pin "14") (pinfunction "RB4/CCP4/PMA1/KBI0/RP7_14") (pintype "passive"))
    )
    (net (code "45") (name "unconnected-(DD1-RB5{slash}CCP5{slash}PMA0{slash}KBI1{slash}RP8-Pad15)") (class "Default")
      (node (ref "DD1") (pin "15") (pinfunction "RB5/CCP5/PMA0/KBI1/RP8_15") (pintype "passive"))
    )
    (net (code "46") (name "unconnected-(DD1-RB6{slash}CCP6{slash}KBI2{slash}PGC{slash}RP9-Pad16)") (class "Default")
      (node (ref "DD1") (pin "16") (pinfunction "RB6/CCP6/KBI2/PGC/RP9_16") (pintype "passive"))
    )
    (net (code "47") (name "unconnected-(DD1-RB7{slash}CCP7{slash}KBI3{slash}PGD{slash}RP10-Pad17)") (class "Default")
      (node (ref "DD1") (pin "17") (pinfunction "RB7/CCP7/KBI3/PGD/RP10_17") (pintype "passive"))
    )
    (net (code "48") (name "unconnected-(DD1-RC2{slash}AN11{slash}C2IND{slash}CTPLS{slash}RP13-Pad36)") (class "Default")
      (node (ref "DD1") (pin "36") (pinfunction "RC2/AN11/C2IND/CTPLS/RP13_36") (pintype "passive"))
    )
    (net (code "49") (name "unconnected-(DD1-RC3{slash}SCK1{slash}SCL1{slash}RP14-Pad37)") (class "Default")
      (node (ref "DD1") (pin "37") (pinfunction "RC3/SCK1/SCL1/RP14_37") (pintype "passive"))
    )
    (net (code "50") (name "unconnected-(DD1-RC4{slash}SDI1{slash}SDA1{slash}RP15-Pad42)") (class "Default")
      (node (ref "DD1") (pin "42") (pinfunction "RC4/SDI1/SDA1/RP15_42") (pintype "passive"))
    )
    (net (code "51") (name "unconnected-(DD1-RC5{slash}SDO1{slash}RP16-Pad43)") (class "Default")
      (node (ref "DD1") (pin "43") (pinfunction "RC5/SDO1/RP16_43") (pintype "passive"))
    )
    (net (code "52") (name "unconnected-(DD1-RC6{slash}CCP9{slash}PMA5{slash}TX1{slash}CK1{slash}RP17-Pad44)") (class "Default")
      (node (ref "DD1") (pin "44") (pinfunction "RC6/CCP9/PMA5/TX1/CK1/RP17_44") (pintype "passive"))
    )
    (net (code "53") (name "unconnected-(DD1-RD0{slash}PMD0{slash}SCL2-Pad38)") (class "Default")
      (node (ref "DD1") (pin "38") (pinfunction "RD0/PMD0/SCL2_38") (pintype "passive"))
    )
    (net (code "54") (name "unconnected-(DD1-RD1{slash}PMD1{slash}SDA2-Pad39)") (class "Default")
      (node (ref "DD1") (pin "39") (pinfunction "RD1/PMD1/SDA2_39") (pintype "passive"))
    )
    (net (code "55") (name "unconnected-(DD1-RD2{slash}PMD2{slash}RP19-Pad40)") (class "Default")
      (node (ref "DD1") (pin "40") (pinfunction "RD2/PMD2/RP19_40") (pintype "passive"))
    )
    (net (code "56") (name "unconnected-(DD1-RD3{slash}PMD3{slash}RP20-Pad41)") (class "Default")
      (node (ref "DD1") (pin "41") (pinfunction "RD3/PMD3/RP20_41") (pintype "passive"))
    )
    (net (code "57") (name "unconnected-(DD1-RD4{slash}PMD4{slash}RP21-Pad2)") (class "Default")
      (node (ref "DD1") (pin "2") (pinfunction "RD4/PMD4/RP21_2") (pintype "passive"))
    )
    (net (code "58") (name "unconnected-(DD1-RD5{slash}PMD5{slash}RP22-Pad3)") (class "Default")
      (node (ref "DD1") (pin "3") (pinfunction "RD5/PMD5/RP22_3") (pintype "passive"))
    )
    (net (code "59") (name "unconnected-(DD1-RD6{slash}PMD6{slash}RP23-Pad4)") (class "Default")
      (node (ref "DD1") (pin "4") (pinfunction "RD6/PMD6/RP23_4") (pintype "passive"))
    )
    (net (code "60") (name "unconnected-(DD1-RD7{slash}PMD7{slash}RP24-Pad5)") (class "Default")
      (node (ref "DD1") (pin "5") (pinfunction "RD7/PMD7/RP24_5") (pintype "passive"))
    )
    (net (code "61") (name "unconnected-(DD1-RE0{slash}AN5{slash}PMRD-Pad25)") (class "Default")
      (node (ref "DD1") (pin "25") (pinfunction "RE0/AN5/PMRD_25") (pintype "passive"))
    )
    (net (code "62") (name "unconnected-(DD1-RE1{slash}AN6{slash}PMWR-Pad26)") (class "Default")
      (node (ref "DD1") (pin "26") (pinfunction "RE1/AN6/PMWR_26") (pintype "passive"))
    )
    (net (code "63") (name "unconnected-(DD1-RE2{slash}AN7{slash}PMCS-Pad27)") (class "Default")
      (node (ref "DD1") (pin "27") (pinfunction "RE2/AN7/PMCS_27") (pintype "passive"))
    )
    (net (code "64") (name "unconnected-(DD1-~{MCLR}-Pad18)") (class "Default")
      (node (ref "DD1") (pin "18") (pinfunction "~{MCLR}_18") (pintype "passive"))
    )
    (net (code "65") (name "unconnected-(T1-Pad1)") (class "Default")
      (node (ref "T1") (pin "1") (pinfunction "1_1") (pintype "passive"))
    )
    (net (code "66") (name "unconnected-(T1-Pad1)_1") (class "Default")
      (node (ref "T1") (pin "1") (pinfunction "1_1") (pintype "passive"))
    )
    (net (code "67") (name "unconnected-(T1-Pad2)") (class "Default")
      (node (ref "T1") (pin "2") (pinfunction "2_2") (pintype "passive"))
    )
    (net (code "68") (name "unconnected-(T1-Pad2)_1") (class "Default")
      (node (ref "T1") (pin "2") (pinfunction "2_2") (pintype "passive"))
    )
  )
)
